# AUDIO.net
KiCad netlist of a schematic drawn in Altium Designer
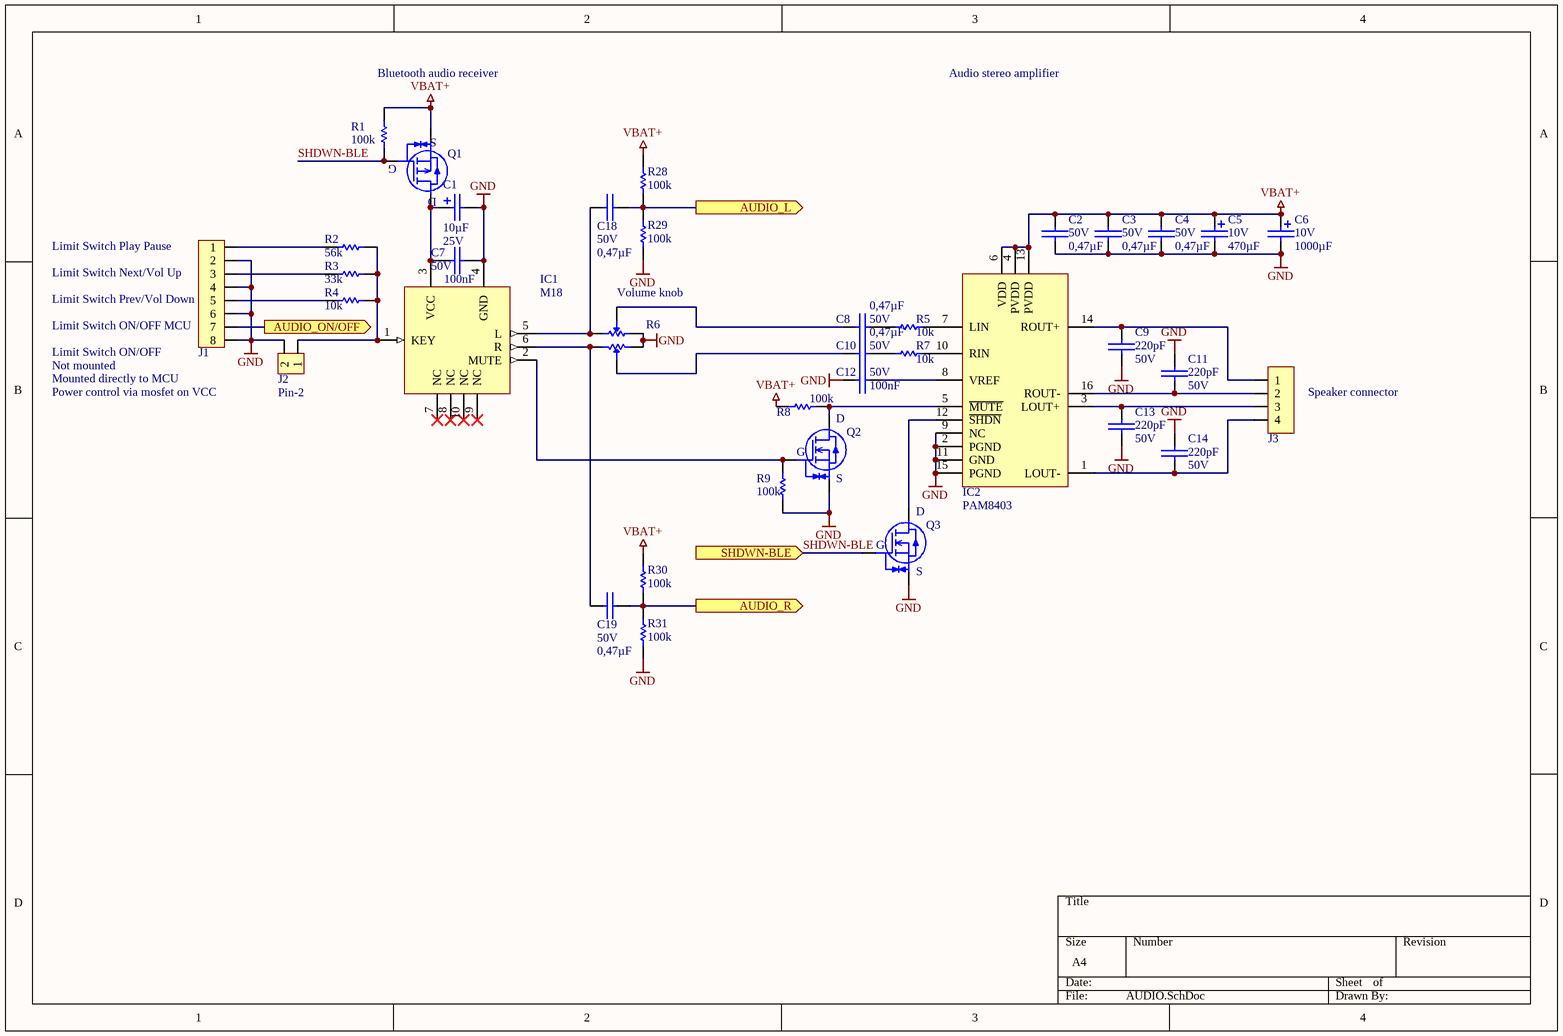
[diagram p0: AUDIO.SchDoc]

(export (version "E")
  (design (tool "Eeschema 10.0.6"))
  (components
    (comp (ref "C1")
      (value "10µF")
      (footprint "CD6.3H12TH")
      (description "CAP ALUM 10UF 20% 25V TH")
      (fields
        (field (name "MANUFACTURER") "Yunxing")
        (field (name "TOLERANCE") "20%")
        (field (name "VOLTAGE") "25V")
      )
      (libsource (lib "js-altium-library") (part "cap-pol"))
    )
    (comp (ref "C2")
      (value "0,47µF")
      (footprint "TH5.08")
      (description "CAP CER TH 0.47µF X7R 50V")
      (fields
        (field (name "MANUFACTURER") "Dersonic")
        (field (name "TOLERANCE") "10%")
        (field (name "VOLTAGE") "50V")
      )
      (libsource (lib "js-altium-library") (part "cap_non_pol"))
    )
    (comp (ref "C3")
      (value "0,47µF")
      (footprint "TH5.08")
      (description "CAP CER TH 0.47µF X7R 50V")
      (fields
        (field (name "MANUFACTURER") "Dersonic")
        (field (name "TOLERANCE") "10%")
        (field (name "VOLTAGE") "50V")
      )
      (libsource (lib "js-altium-library") (part "cap_non_pol"))
    )
    (comp (ref "C4")
      (value "0,47µF")
      (footprint "TH5.08")
      (description "CAP CER TH 0.47µF X7R 50V")
      (fields
        (field (name "MANUFACTURER") "Dersonic")
        (field (name "TOLERANCE") "10%")
        (field (name "VOLTAGE") "50V")
      )
      (libsource (lib "js-altium-library") (part "cap_non_pol"))
    )
    (comp (ref "C5")
      (value "470µF")
      (footprint "CD6.3H12TH")
      (description "CAP ALUM 470UF 20% 10V TH")
      (fields
        (field (name "MANUFACTURER") "AISHI(Aihua Group)")
        (field (name "TOLERANCE") "20%")
        (field (name "VOLTAGE") "10V")
      )
      (libsource (lib "js-altium-library") (part "cap-pol"))
    )
    (comp (ref "C6")
      (value "1000µF")
      (footprint "CD8H12TH")
      (description "CAP ALUM 1000UF 20% 10V TH")
      (fields
        (field (name "MANUFACTURER") "AISHI(Aihua Group)")
        (field (name "TOLERANCE") "20%")
        (field (name "VOLTAGE") "10V")
      )
      (libsource (lib "js-altium-library") (part "cap-pol"))
    )
    (comp (ref "C7")
      (value "100nF")
      (footprint "TH5.08")
      (description "CAP CER TH 100nF X7R 50V")
      (fields
        (field (name "MANUFACTURER") "FH")
        (field (name "TOLERANCE") "10%")
        (field (name "VOLTAGE") "50V")
      )
      (libsource (lib "js-altium-library") (part "cap_non_pol"))
    )
    (comp (ref "C8")
      (value "0,47µF")
      (footprint "TH5.08")
      (description "CAP CER TH 0.47µF X7R 50V")
      (fields
        (field (name "MANUFACTURER") "Dersonic")
        (field (name "TOLERANCE") "10%")
        (field (name "VOLTAGE") "50V")
      )
      (libsource (lib "js-altium-library") (part "cap_non_pol"))
    )
    (comp (ref "C9")
      (value "220pF")
      (footprint "TH5.08")
      (description "CAP CER TH 100nF X7R 50V")
      (fields
        (field (name "MANUFACTURER") "WMEC")
        (field (name "TOLERANCE") "10%")
        (field (name "VOLTAGE") "50V")
      )
      (libsource (lib "js-altium-library") (part "cap_non_pol"))
    )
    (comp (ref "C10")
      (value "0,47µF")
      (footprint "TH5.08")
      (description "CAP CER TH 0.47µF X7R 50V")
      (fields
        (field (name "MANUFACTURER") "Dersonic")
        (field (name "TOLERANCE") "10%")
        (field (name "VOLTAGE") "50V")
      )
      (libsource (lib "js-altium-library") (part "cap_non_pol"))
    )
    (comp (ref "C11")
      (value "220pF")
      (footprint "TH5.08")
      (description "CAP CER TH 100nF X7R 50V")
      (fields
        (field (name "MANUFACTURER") "WMEC")
        (field (name "TOLERANCE") "10%")
        (field (name "VOLTAGE") "50V")
      )
      (libsource (lib "js-altium-library") (part "cap_non_pol"))
    )
    (comp (ref "C12")
      (value "100nF")
      (footprint "TH5.08")
      (description "CAP CER TH 100nF X7R 50V")
      (fields
        (field (name "MANUFACTURER") "FH")
        (field (name "TOLERANCE") "10%")
        (field (name "VOLTAGE") "50V")
      )
      (libsource (lib "js-altium-library") (part "cap_non_pol"))
    )
    (comp (ref "C13")
      (value "220pF")
      (footprint "TH5.08")
      (description "CAP CER TH 100nF X7R 50V")
      (fields
        (field (name "MANUFACTURER") "WMEC")
        (field (name "TOLERANCE") "10%")
        (field (name "VOLTAGE") "50V")
      )
      (libsource (lib "js-altium-library") (part "cap_non_pol"))
    )
    (comp (ref "C14")
      (value "220pF")
      (footprint "TH5.08")
      (description "CAP CER TH 100nF X7R 50V")
      (fields
        (field (name "MANUFACTURER") "WMEC")
        (field (name "TOLERANCE") "10%")
        (field (name "VOLTAGE") "50V")
      )
      (libsource (lib "js-altium-library") (part "cap_non_pol"))
    )
    (comp (ref "C18")
      (value "0,47µF")
      (footprint "TH5.08")
      (description "CAP CER TH 0.47µF X7R 50V")
      (fields
        (field (name "MANUFACTURER") "Dersonic")
        (field (name "TOLERANCE") "10%")
        (field (name "VOLTAGE") "50V")
      )
      (libsource (lib "js-altium-library") (part "cap_non_pol"))
    )
    (comp (ref "C19")
      (value "0,47µF")
      (footprint "TH5.08")
      (description "CAP CER TH 0.47µF X7R 50V")
      (fields
        (field (name "MANUFACTURER") "Dersonic")
        (field (name "TOLERANCE") "10%")
        (field (name "VOLTAGE") "50V")
      )
      (libsource (lib "js-altium-library") (part "cap_non_pol"))
    )
    (comp (ref "IC1")
      (value "M18")
      (footprint "M18")
      (description "M18 Bluetooth 4.2 Audio-receiver Module Lossless")
      (libsource (lib "js-altium-library") (part "M18"))
    )
    (comp (ref "IC2")
      (value "PAM8403")
      (footprint "SOIC-16")
      (description "3W x 2 RL=4Ω 2.5V ~ 5.5V (stereo) Class D SOIC-16 Audio Power OpAmps")
      (fields (field (name "MANUFACTURER") "Diodes Incorporated"))
      (libsource (lib "js-altium-library") (part "PAM8403"))
    )
    (comp (ref "J1")
      (value "Pin-8")
      (footprint "2205114-3")
      (description "CA 200MM 08 POS. MOW-PB M-M VALU")
      (fields (field (name "MANUFACTURER") "TE Connectivity AMP Connectors"))
      (libsource (lib "js-altium-library") (part "Pin-8"))
    )
    (comp (ref "J2")
      (value "Pin-2")
      (footprint "2-PIN")
      (description "'CONN 2 PIN SOLDER PADS")
      (libsource (lib "js-altium-library") (part "Pin-2"))
    )
    (comp (ref "J3")
      (value "Pin-4")
      (footprint "B4B-PH-K")
      (description "CONN HEADER VERT 4POS 2MM")
      (fields (field (name "MANUFACTURER") "JST Sales America Inc."))
      (libsource (lib "js-altium-library") (part "Pin-4"))
    )
    (comp (ref "Q1")
      (value "P_CH_MOSFET2")
      (footprint "TO-220AB")
      (description "MOSFET P-CH 60V 17A TO-220AB")
      (fields (field (name "MANUFACTURER") "HUASHUO"))
      (libsource (lib "js-altium-library") (part "P_CH_MOSFET2"))
    )
    (comp (ref "Q2")
      (value "N_CH_MOSFET2")
      (footprint "TO-92")
      (description "MOSFET N-CH 60V 0.2A TO-92")
      (fields (field (name "MANUFACTURER") "Changjiang Electronics Tech (CJ)"))
      (libsource (lib "js-altium-library") (part "N_CH_MOSFET2"))
    )
    (comp (ref "Q3")
      (value "N_CH_MOSFET2")
      (footprint "TO-92")
      (description "MOSFET N-CH 60V 0.2A TO-92")
      (fields (field (name "MANUFACTURER") "Changjiang Electronics Tech (CJ)"))
      (libsource (lib "js-altium-library") (part "N_CH_MOSFET2"))
    )
    (comp (ref "R1")
      (value "100k")
      (footprint "TH6.3")
      (description "RES TH 100k OHM 5% 1/4W")
      (fields (field (name "MANUFACTURER") "VO") (field (name "TOLERANCE") "5%"))
      (libsource (lib "js-altium-library") (part "resistor"))
    )
    (comp (ref "R2")
      (value "56k")
      (footprint "TH6.3")
      (description "RES TH 56k OHM 5% 1/4W")
      (fields (field (name "MANUFACTURER") "VO") (field (name "TOLERANCE") "5%"))
      (libsource (lib "js-altium-library") (part "resistor"))
    )
    (comp (ref "R3")
      (value "33k")
      (footprint "TH6.3")
      (description "RES TH 33k OHM 5% 1/4W")
      (fields (field (name "MANUFACTURER") "VO") (field (name "TOLERANCE") "5%"))
      (libsource (lib "js-altium-library") (part "resistor"))
    )
    (comp (ref "R4")
      (value "10k")
      (footprint "TH6.3")
      (description "RES TH 10k OHM 5% 1/4W")
      (fields (field (name "MANUFACTURER") "VO") (field (name "TOLERANCE") "5%"))
      (libsource (lib "js-altium-library") (part "resistor"))
    )
    (comp (ref "R5")
      (value "10k")
      (footprint "TH6.3")
      (description "RES TH 10k OHM 5% 1/4W")
      (fields (field (name "MANUFACTURER") "VO") (field (name "TOLERANCE") "5%"))
      (libsource (lib "js-altium-library") (part "resistor"))
    )
    (comp (ref "R6")
      (value "2-gang potentiometer")
      (footprint "P140KV1-F25BR10K")
      (description "POT 10K OHM 1/20W PLASTIC LINEAR")
      (fields (field (name "MANUFACTURER") "TT Electronics/BI") (field (name "POWER") "1/20W"))
      (libsource (lib "js-altium-library") (part "2-gang potentiometer"))
    )
    (comp (ref "R7")
      (value "10k")
      (footprint "TH6.3")
      (description "RES TH 10k OHM 5% 1/4W")
      (fields (field (name "MANUFACTURER") "VO") (field (name "TOLERANCE") "5%"))
      (libsource (lib "js-altium-library") (part "resistor"))
    )
    (comp (ref "R8")
      (value "100k")
      (footprint "TH6.3")
      (description "RES TH 100k OHM 5% 1/4W")
      (fields (field (name "MANUFACTURER") "VO") (field (name "TOLERANCE") "5%"))
      (libsource (lib "js-altium-library") (part "resistor"))
    )
    (comp (ref "R9")
      (value "100k")
      (footprint "TH6.3")
      (description "RES TH 100k OHM 5% 1/4W")
      (fields (field (name "MANUFACTURER") "VO") (field (name "TOLERANCE") "5%"))
      (libsource (lib "js-altium-library") (part "resistor"))
    )
    (comp (ref "R28")
      (value "100k")
      (footprint "TH6.3")
      (description "RES TH 100k OHM 5% 1/4W")
      (fields (field (name "MANUFACTURER") "VO") (field (name "TOLERANCE") "5%"))
      (libsource (lib "js-altium-library") (part "resistor"))
    )
    (comp (ref "R29")
      (value "100k")
      (footprint "TH6.3")
      (description "RES TH 100k OHM 5% 1/4W")
      (fields (field (name "MANUFACTURER") "VO") (field (name "TOLERANCE") "5%"))
      (libsource (lib "js-altium-library") (part "resistor"))
    )
    (comp (ref "R30")
      (value "100k")
      (footprint "TH6.3")
      (description "RES TH 100k OHM 5% 1/4W")
      (fields (field (name "MANUFACTURER") "VO") (field (name "TOLERANCE") "5%"))
      (libsource (lib "js-altium-library") (part "resistor"))
    )
    (comp (ref "R31")
      (value "100k")
      (footprint "TH6.3")
      (description "RES TH 100k OHM 5% 1/4W")
      (fields (field (name "MANUFACTURER") "VO") (field (name "TOLERANCE") "5%"))
      (libsource (lib "js-altium-library") (part "resistor"))
    )
  )
  (nets
    (net (code "1") (name "/AUDIO_L") (class "Default")
      (node (ref "C18") (pin "1") (pinfunction "1_1") (pintype "passive"))
      (node (ref "R28") (pin "1") (pinfunction "1_1") (pintype "passive"))
      (node (ref "R29") (pin "2") (pinfunction "2_2") (pintype "passive"))
    )
    (net (code "2") (name "/AUDIO_ON{slash}OFF") (class "Default")
      (node (ref "J1") (pin "7") (pinfunction "7_7") (pintype "passive"))
    )
    (net (code "3") (name "/AUDIO_R") (class "Default")
      (node (ref "C19") (pin "1") (pinfunction "1_1") (pintype "passive"))
      (node (ref "R30") (pin "1") (pinfunction "1_1") (pintype "passive"))
      (node (ref "R31") (pin "2") (pinfunction "2_2") (pintype "passive"))
    )
    (net (code "4") (name "/SHDWN-BLE") (class "Default")
      (node (ref "Q1") (pin "G") (pinfunction "G_G") (pintype "passive"))
      (node (ref "Q3") (pin "G") (pinfunction "G_G") (pintype "passive"))
      (node (ref "R1") (pin "1") (pinfunction "1_1") (pintype "passive"))
    )
    (net (code "5") (name "GND") (class "Default")
      (node (ref "C1") (pin "-") (pinfunction "-_-") (pintype "passive"))
      (node (ref "C11") (pin "1") (pinfunction "1_1") (pintype "passive"))
      (node (ref "C12") (pin "2") (pinfunction "2_2") (pintype "passive"))
      (node (ref "C13") (pin "2") (pinfunction "2_2") (pintype "passive"))
      (node (ref "C14") (pin "1") (pinfunction "1_1") (pintype "passive"))
      (node (ref "C2") (pin "2") (pinfunction "2_2") (pintype "passive"))
      (node (ref "C3") (pin "2") (pinfunction "2_2") (pintype "passive"))
      (node (ref "C4") (pin "2") (pinfunction "2_2") (pintype "passive"))
      (node (ref "C5") (pin "-") (pinfunction "-_-") (pintype "passive"))
      (node (ref "C6") (pin "-") (pinfunction "-_-") (pintype "passive"))
      (node (ref "C7") (pin "2") (pinfunction "2_2") (pintype "passive"))
      (node (ref "C9") (pin "2") (pinfunction "2_2") (pintype "passive"))
      (node (ref "IC1") (pin "4") (pinfunction "GND_4") (pintype "power_in"))
      (node (ref "IC2") (pin "11") (pinfunction "GND_11") (pintype "passive"))
      (node (ref "IC2") (pin "15") (pinfunction "PGND_15") (pintype "passive"))
      (node (ref "IC2") (pin "2") (pinfunction "PGND_2") (pintype "passive"))
      (node (ref "IC2") (pin "9") (pinfunction "NC_9") (pintype "passive"))
      (node (ref "J1") (pin "2") (pinfunction "2_2") (pintype "passive"))
      (node (ref "J1") (pin "4") (pinfunction "4_4") (pintype "passive"))
      (node (ref "J1") (pin "6") (pinfunction "6_6") (pintype "passive"))
      (node (ref "J1") (pin "8") (pinfunction "8_8") (pintype "passive"))
      (node (ref "J2") (pin "2") (pinfunction "2_2") (pintype "passive"))
      (node (ref "Q2") (pin "S") (pinfunction "S_S") (pintype "passive"))
      (node (ref "Q3") (pin "S") (pinfunction "S_S") (pintype "passive"))
      (node (ref "R29") (pin "1") (pinfunction "1_1") (pintype "passive"))
      (node (ref "R31") (pin "1") (pinfunction "1_1") (pintype "passive"))
      (node (ref "R6") (pin "1") (pinfunction "1_1") (pintype "passive"))
      (node (ref "R6") (pin "2") (pinfunction "2_2") (pintype "passive"))
      (node (ref "R9") (pin "1") (pinfunction "1_1") (pintype "passive"))
    )
    (net (code "6") (name "Net-(C8-Pad1)") (class "Default")
      (node (ref "C8") (pin "1") (pinfunction "1_1") (pintype "passive"))
      (node (ref "R5") (pin "2") (pinfunction "2_2") (pintype "passive"))
    )
    (net (code "7") (name "Net-(C8-Pad2)") (class "Default")
      (node (ref "C8") (pin "2") (pinfunction "2_2") (pintype "passive"))
      (node (ref "R6") (pin "4") (pinfunction "4_4") (pintype "passive"))
    )
    (net (code "8") (name "Net-(C10-Pad1)") (class "Default")
      (node (ref "C10") (pin "1") (pinfunction "1_1") (pintype "passive"))
      (node (ref "R7") (pin "2") (pinfunction "2_2") (pintype "passive"))
    )
    (net (code "9") (name "Net-(C10-Pad2)") (class "Default")
      (node (ref "C10") (pin "2") (pinfunction "2_2") (pintype "passive"))
      (node (ref "R6") (pin "3") (pinfunction "3_3") (pintype "passive"))
    )
    (net (code "10") (name "Net-(IC1-KEY)") (class "Default")
      (node (ref "IC1") (pin "1") (pinfunction "KEY_1") (pintype "input"))
      (node (ref "J2") (pin "1") (pinfunction "1_1") (pintype "passive"))
      (node (ref "R2") (pin "1") (pinfunction "1_1") (pintype "passive"))
      (node (ref "R3") (pin "1") (pinfunction "1_1") (pintype "passive"))
      (node (ref "R4") (pin "1") (pinfunction "1_1") (pintype "passive"))
    )
    (net (code "11") (name "Net-(IC1-L)") (class "Default")
      (node (ref "C18") (pin "2") (pinfunction "2_2") (pintype "passive"))
      (node (ref "IC1") (pin "5") (pinfunction "L_5") (pintype "output"))
      (node (ref "R6") (pin "6") (pinfunction "6_6") (pintype "passive"))
    )
    (net (code "12") (name "Net-(IC1-MUTE)") (class "Default")
      (node (ref "IC1") (pin "2") (pinfunction "MUTE_2") (pintype "output"))
      (node (ref "Q2") (pin "G") (pinfunction "G_G") (pintype "passive"))
      (node (ref "R9") (pin "2") (pinfunction "2_2") (pintype "passive"))
    )
    (net (code "13") (name "Net-(IC1-R)") (class "Default")
      (node (ref "C19") (pin "2") (pinfunction "2_2") (pintype "passive"))
      (node (ref "IC1") (pin "6") (pinfunction "R_6") (pintype "output"))
      (node (ref "R6") (pin "5") (pinfunction "5_5") (pintype "passive"))
    )
    (net (code "14") (name "Net-(IC1-VCC)") (class "Default")
      (node (ref "C1") (pin "+") (pinfunction "+_+") (pintype "passive"))
      (node (ref "C7") (pin "1") (pinfunction "1_1") (pintype "passive"))
      (node (ref "IC1") (pin "3") (pinfunction "VCC_3") (pintype "power_in"))
      (node (ref "Q1") (pin "D") (pinfunction "D_D") (pintype "passive"))
    )
    (net (code "15") (name "Net-(IC2-LIN)") (class "Default")
      (node (ref "IC2") (pin "7") (pinfunction "LIN_7") (pintype "passive"))
      (node (ref "R5") (pin "1") (pinfunction "1_1") (pintype "passive"))
    )
    (net (code "16") (name "Net-(IC2-LOUT+)") (class "Default")
      (node (ref "C13") (pin "1") (pinfunction "1_1") (pintype "passive"))
      (node (ref "IC2") (pin "3") (pinfunction "LOUT+_3") (pintype "passive"))
      (node (ref "J3") (pin "3") (pinfunction "3_3") (pintype "passive"))
    )
    (net (code "17") (name "Net-(IC2-LOUT-)") (class "Default")
      (node (ref "C14") (pin "2") (pinfunction "2_2") (pintype "passive"))
      (node (ref "IC2") (pin "1") (pinfunction "LOUT-_1") (pintype "passive"))
      (node (ref "J3") (pin "4") (pinfunction "4_4") (pintype "passive"))
    )
    (net (code "18") (name "Net-(IC2-RIN)") (class "Default")
      (node (ref "IC2") (pin "10") (pinfunction "RIN_10") (pintype "passive"))
      (node (ref "R7") (pin "1") (pinfunction "1_1") (pintype "passive"))
    )
    (net (code "19") (name "Net-(IC2-ROUT+)") (class "Default")
      (node (ref "C9") (pin "1") (pinfunction "1_1") (pintype "passive"))
      (node (ref "IC2") (pin "14") (pinfunction "ROUT+_14") (pintype "passive"))
      (node (ref "J3") (pin "1") (pinfunction "1_1") (pintype "passive"))
    )
    (net (code "20") (name "Net-(IC2-ROUT-)") (class "Default")
      (node (ref "C11") (pin "2") (pinfunction "2_2") (pintype "passive"))
      (node (ref "IC2") (pin "16") (pinfunction "ROUT-_16") (pintype "passive"))
      (node (ref "J3") (pin "2") (pinfunction "2_2") (pintype "passive"))
    )
    (net (code "21") (name "Net-(IC2-VREF)") (class "Default")
      (node (ref "C12") (pin "1") (pinfunction "1_1") (pintype "passive"))
      (node (ref "IC2") (pin "8") (pinfunction "VREF_8") (pintype "passive"))
    )
    (net (code "22") (name "Net-(IC2-~{MUTE})") (class "Default")
      (node (ref "IC2") (pin "5") (pinfunction "~{MUTE}_5") (pintype "passive"))
      (node (ref "Q2") (pin "D") (pinfunction "D_D") (pintype "passive"))
      (node (ref "R8") (pin "2") (pinfunction "2_2") (pintype "passive"))
    )
    (net (code "23") (name "Net-(IC2-~{SHDN})") (class "Default")
      (node (ref "IC2") (pin "12") (pinfunction "~{SHDN}_12") (pintype "passive"))
      (node (ref "Q3") (pin "D") (pinfunction "D_D") (pintype "passive"))
    )
    (net (code "24") (name "Net-(J1-Pad1)") (class "Default")
      (node (ref "J1") (pin "1") (pinfunction "1_1") (pintype "passive"))
      (node (ref "R2") (pin "2") (pinfunction "2_2") (pintype "passive"))
    )
    (net (code "25") (name "Net-(J1-Pad3)") (class "Default")
      (node (ref "J1") (pin "3") (pinfunction "3_3") (pintype "passive"))
      (node (ref "R3") (pin "2") (pinfunction "2_2") (pintype "passive"))
    )
    (net (code "26") (name "Net-(J1-Pad5)") (class "Default")
      (node (ref "J1") (pin "5") (pinfunction "5_5") (pintype "passive"))
      (node (ref "R4") (pin "2") (pinfunction "2_2") (pintype "passive"))
    )
    (net (code "27") (name "VBAT+") (class "Default")
      (node (ref "C2") (pin "1") (pinfunction "1_1") (pintype "passive"))
      (node (ref "C3") (pin "1") (pinfunction "1_1") (pintype "passive"))
      (node (ref "C4") (pin "1") (pinfunction "1_1") (pintype "passive"))
      (node (ref "C5") (pin "+") (pinfunction "+_+") (pintype "passive"))
      (node (ref "C6") (pin "+") (pinfunction "+_+") (pintype "passive"))
      (node (ref "IC2") (pin "13") (pinfunction "PVDD_13") (pintype "passive"))
      (node (ref "IC2") (pin "4") (pinfunction "PVDD_4") (pintype "passive"))
      (node (ref "IC2") (pin "6") (pinfunction "VDD_6") (pintype "passive"))
      (node (ref "Q1") (pin "S") (pinfunction "S_S") (pintype "passive"))
      (node (ref "R1") (pin "2") (pinfunction "2_2") (pintype "passive"))
      (node (ref "R28") (pin "2") (pinfunction "2_2") (pintype "passive"))
      (node (ref "R30") (pin "2") (pinfunction "2_2") (pintype "passive"))
      (node (ref "R8") (pin "1") (pinfunction "1_1") (pintype "passive"))
    )
    (net (code "28") (name "unconnected-(IC1-NC-Pad7)") (class "Default")
      (node (ref "IC1") (pin "7") (pinfunction "NC_7") (pintype "passive+no_connect"))
    )
    (net (code "29") (name "unconnected-(IC1-NC-Pad8)") (class "Default")
      (node (ref "IC1") (pin "8") (pinfunction "NC_8") (pintype "passive+no_connect"))
    )
    (net (code "30") (name "unconnected-(IC1-NC-Pad9)") (class "Default")
      (node (ref "IC1") (pin "9") (pinfunction "NC_9") (pintype "passive+no_connect"))
    )
    (net (code "31") (name "unconnected-(IC1-NC-Pad10)") (class "Default")
      (node (ref "IC1") (pin "10") (pinfunction "NC_10") (pintype "passive+no_connect"))
    )
  )
)
